# Sheet1.net
KiCad netlist of a schematic drawn in Altium Designer
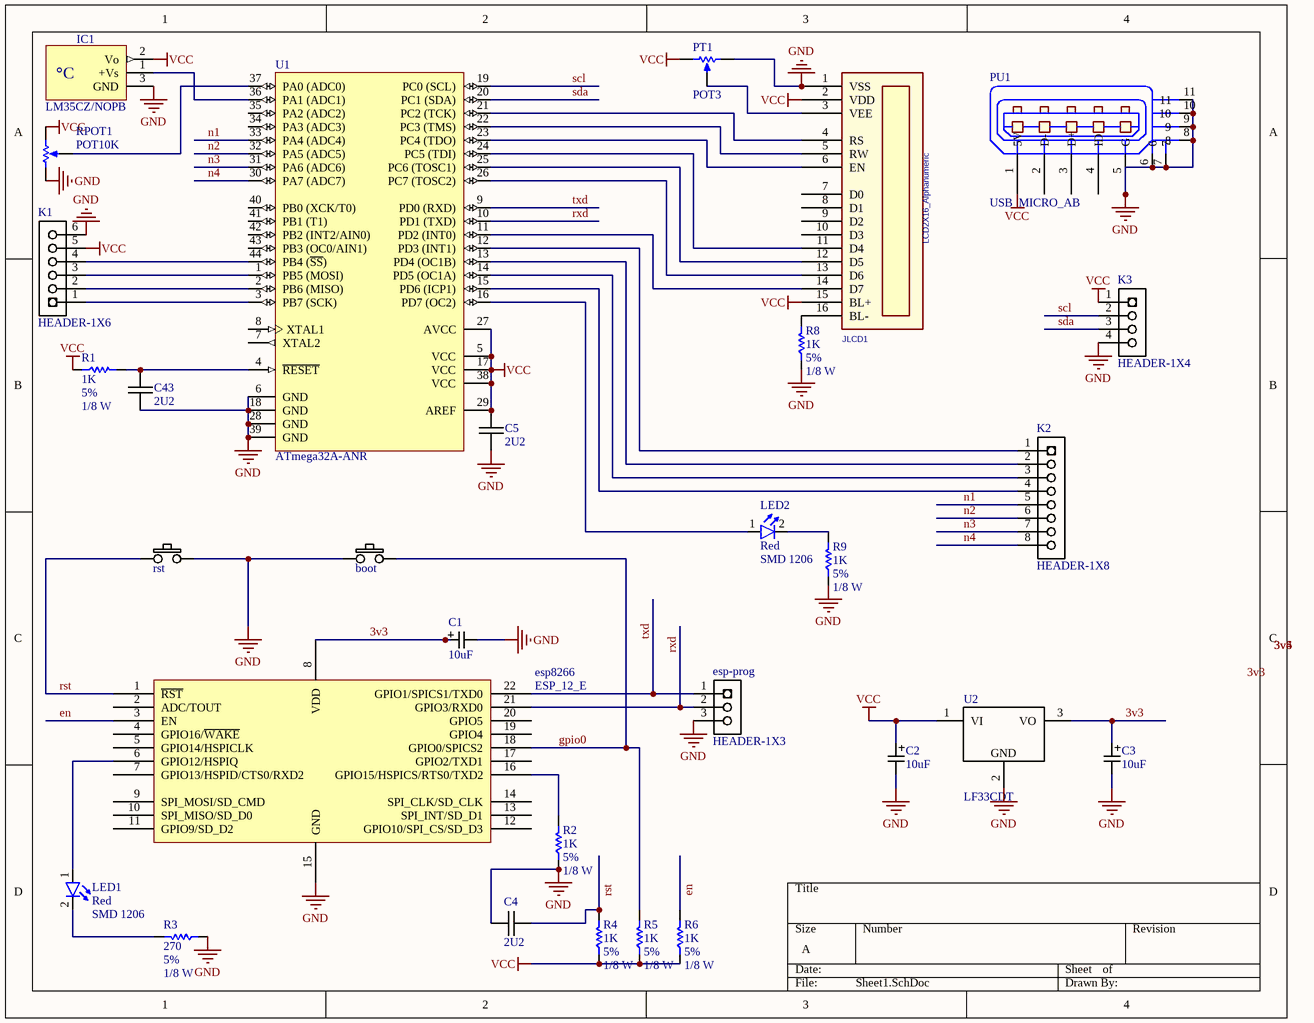
[diagram p0: Sheet1.SchDoc]

(export (version "E")
  (design (tool "Eeschema 10.0.6"))
  (components
    (comp (ref "boot")
      (value "SW-PB-BLACK-SMD")
      (footprint "SW-PB-SMD")
      (description "PUSHBUTTON SWITCH 6MM SMD")
      (libsource (lib "vh_altium_library") (part "SW-PB-BLACK-SMD"))
    )
    (comp (ref "C1")
      (value "10uF")
      (footprint "CAP-B")
      (description "tantalium capacitor")
      (fields (field (name "VOLTAGE") "16V"))
      (libsource (lib "amir_altium_lib") (part "cap"))
    )
    (comp (ref "C2")
      (value "10uF")
      (footprint "CAP-B")
      (description "tantalium capacitor")
      (fields (field (name "VOLTAGE") "16V"))
      (libsource (lib "amir_altium_lib") (part "cap"))
    )
    (comp (ref "C3")
      (value "10uF")
      (footprint "CAP-B")
      (description "tantalium capacitor")
      (fields (field (name "VOLTAGE") "16V"))
      (libsource (lib "amir_altium_lib") (part "cap"))
    )
    (comp (ref "C4")
      (value "2U2")
      (footprint "1206C-GENERIC")
      (description "CAPACITOR 0603 CERAMIC")
      (libsource (lib "vh_altium_library") (part "1206C-2U2-50V"))
    )
    (comp (ref "C5")
      (value "2U2")
      (footprint "1206C-GENERIC")
      (description "CAPACITOR 0603 CERAMIC")
      (libsource (lib "vh_altium_library") (part "1206C-2U2-50V"))
    )
    (comp (ref "C43")
      (value "2U2")
      (footprint "1206C-GENERIC")
      (description "CAPACITOR 0603 CERAMIC")
      (libsource (lib "vh_altium_library") (part "1206C-2U2-50V"))
    )
    (comp (ref "esp-prog")
      (value "HEADER-1X3")
      (footprint "HEADER-1X3")
      (libsource (lib "vh_altium_library") (part "HEADER-1X3"))
    )
    (comp (ref "esp8266")
      (value "ESP_12_E")
      (footprint "ESP_12_E")
      (description "ESP-12 Wi-Fi Module by AI-Thinker")
      (libsource (lib "Morteza lib") (part "ESP_12_E"))
    )
    (comp (ref "IC1")
      (value "LM35CZ/NOPB")
      (footprint "TO-92AA-P127")
      (description "Precision Centigrade Temperature Sensor")
      (fields (field (name "MANUFACTURER") "NATIONAL SEMICONDUCTOR") (field (name "AUTHOR") "CERN DEM JLC"))
      (libsource (lib "Sensors") (part "LM35CZ/NOPB"))
    )
    (comp (ref "JLCD1") (value "LCD2X16_Alphanumeric") (libsource (lib "ALL") (part "LCD2X16_Alphanumeric")))
    (comp (ref "K1")
      (value "HEADER-1X6")
      (footprint "HEADER-1X6")
      (libsource (lib "vh_altium_library") (part "HEADER-1X6"))
    )
    (comp (ref "K2")
      (value "HEADER-1X8")
      (footprint "HEADER-1X8")
      (libsource (lib "vh_altium_library") (part "HEADER-1X8"))
    )
    (comp (ref "K3")
      (value "HEADER-1X4")
      (footprint "HEADER-1X4")
      (libsource (lib "vh_altium_library") (part "HEADER-1X4"))
    )
    (comp (ref "LED1")
      (value "Red")
      (footprint "LED SMD 1206")
      (description "LED")
      (fields
        (field (name "COLOR") "Red")
        (field (name "SIZE") "SMD 1206")
        (field (name "DESIGNER") "Saeid Jorablo")
      )
      (libsource (lib "Electrovolt Lib") (part "LED"))
    )
    (comp (ref "LED2")
      (value "Red")
      (footprint "LED SMD 1206")
      (description "LED")
      (fields
        (field (name "COLOR") "Red")
        (field (name "SIZE") "SMD 1206")
        (field (name "DESIGNER") "Saeid Jorablo")
      )
      (libsource (lib "Electrovolt Lib") (part "LED"))
    )
    (comp (ref "PT1")
      (value "POT3")
      (footprint "POT3")
      (description "Variable Potentiometer top adjust")
      (fields (field (name "DESIGNER") "Seyed Mohsen Ghasemian"))
      (libsource (lib "usefully_Library") (part "POT3"))
    )
    (comp (ref "PU1")
      (value "USB_MICRO_AB")
      (footprint "UUSB_AB_BM_SHS")
      (libsource (lib "ALL") (part "USB_MICRO_AB"))
    )
    (comp (ref "R1")
      (value "1K")
      (footprint "RES 1206 (3216X08L)")
      (description "Resistor")
      (fields (field (name "TOLERANCE") "5%") (field (name "POWER") "1/8 W"))
      (libsource (lib "Electrovolt Lib") (part "Resistor"))
    )
    (comp (ref "R2")
      (value "1K")
      (footprint "RES 1206 (3216X08L)")
      (description "Resistor")
      (fields (field (name "TOLERANCE") "5%") (field (name "POWER") "1/8 W"))
      (libsource (lib "Electrovolt Lib") (part "Resistor"))
    )
    (comp (ref "R3")
      (value "270")
      (footprint "RES 1206 (3216X08L)")
      (description "Resistor")
      (fields (field (name "TOLERANCE") "5%") (field (name "POWER") "1/8 W"))
      (libsource (lib "Electrovolt Lib") (part "Resistor"))
    )
    (comp (ref "R4")
      (value "1K")
      (footprint "RES 1206 (3216X08L)")
      (description "Resistor")
      (fields (field (name "TOLERANCE") "5%") (field (name "POWER") "1/8 W"))
      (libsource (lib "Electrovolt Lib") (part "Resistor"))
    )
    (comp (ref "R5")
      (value "1K")
      (footprint "RES 1206 (3216X08L)")
      (description "Resistor")
      (fields (field (name "TOLERANCE") "5%") (field (name "POWER") "1/8 W"))
      (libsource (lib "Electrovolt Lib") (part "Resistor"))
    )
    (comp (ref "R6")
      (value "1K")
      (footprint "RES 1206 (3216X08L)")
      (description "Resistor")
      (fields (field (name "TOLERANCE") "5%") (field (name "POWER") "1/8 W"))
      (libsource (lib "Electrovolt Lib") (part "Resistor"))
    )
    (comp (ref "R8")
      (value "1K")
      (footprint "RES 1206 (3216X08L)")
      (description "Resistor")
      (fields (field (name "TOLERANCE") "5%") (field (name "POWER") "1/8 W"))
      (libsource (lib "Electrovolt Lib") (part "Resistor"))
    )
    (comp (ref "R9")
      (value "1K")
      (footprint "RES 1206 (3216X08L)")
      (description "Resistor")
      (fields (field (name "TOLERANCE") "5%") (field (name "POWER") "1/8 W"))
      (libsource (lib "Electrovolt Lib") (part "Resistor"))
    )
    (comp (ref "RPOT1")
      (value "POT10K")
      (footprint "VOL_R")
      (description "Potentiometer")
      (fields (field (name "PUBLISHER") "Altium Limited"))
      (libsource (lib "ALL") (part "RPot"))
    )
    (comp (ref "rst")
      (value "SW-PB-BLACK-SMD")
      (footprint "SW-PB-SMD")
      (description "PUSHBUTTON SWITCH 6MM SMD")
      (libsource (lib "vh_altium_library") (part "SW-PB-BLACK-SMD"))
    )
    (comp (ref "U1")
      (value "ATmega32A-ANR")
      (footprint "44A_N")
      (libsource (lib "Atmel Microcontroller megaAVR") (part "ATmega32A-ANR"))
    )
    (comp (ref "U2")
      (value "LF33CDT")
      (footprint "DPAK")
      (description "Low Drop Voltage Regulator 3.3V")
      (libsource (lib "vh_altium_library") (part "LF33CDT"))
    )
  )
  (nets
    (net (code "1") (name "/3v3") (class "Default")
      (node (ref "C1") (pin "1") (pintype "passive"))
      (node (ref "C3") (pin "1") (pintype "passive"))
      (node (ref "U2") (pin "3") (pinfunction "VO_3") (pintype "passive"))
      (node (ref "esp8266") (pin "8") (pinfunction "VDD_8") (pintype "passive"))
    )
    (net (code "3") (name "/en") (class "Default")
      (node (ref "R6") (pin "2") (pinfunction "2_2") (pintype "passive"))
      (node (ref "esp8266") (pin "3") (pinfunction "EN_3") (pintype "passive"))
    )
    (net (code "4") (name "/gpio0") (class "Default")
      (node (ref "R5") (pin "2") (pinfunction "2_2") (pintype "passive"))
      (node (ref "boot") (pin "2") (pintype "passive"))
      (node (ref "esp8266") (pin "18") (pinfunction "GPIO0/SPICS2_18") (pintype "passive"))
    )
    (net (code "5") (name "/n1") (class "Default")
      (node (ref "K2") (pin "5") (pintype "passive"))
      (node (ref "U1") (pin "33") (pinfunction "PA4_(ADC4)_33") (pintype "bidirectional"))
    )
    (net (code "6") (name "/n2") (class "Default")
      (node (ref "K2") (pin "6") (pintype "passive"))
      (node (ref "U1") (pin "32") (pinfunction "PA5_(ADC5)_32") (pintype "bidirectional"))
    )
    (net (code "7") (name "/n3") (class "Default")
      (node (ref "K2") (pin "7") (pintype "passive"))
      (node (ref "U1") (pin "31") (pinfunction "PA6_(ADC6)_31") (pintype "bidirectional"))
    )
    (net (code "8") (name "/n4") (class "Default")
      (node (ref "K2") (pin "8") (pintype "passive"))
      (node (ref "U1") (pin "30") (pinfunction "PA7_(ADC7)_30") (pintype "bidirectional"))
    )
    (net (code "9") (name "/rst") (class "Default")
      (node (ref "C4") (pin "1") (pintype "passive"))
      (node (ref "R4") (pin "2") (pinfunction "2_2") (pintype "passive"))
      (node (ref "esp8266") (pin "1") (pinfunction "~{RST}_1") (pintype "passive"))
      (node (ref "rst") (pin "1") (pintype "passive"))
    )
    (net (code "10") (name "/rxd") (class "Default")
      (node (ref "U1") (pin "10") (pinfunction "PD1_(TXD)_10") (pintype "bidirectional"))
      (node (ref "esp-prog") (pin "2") (pintype "passive"))
      (node (ref "esp8266") (pin "21") (pinfunction "GPIO3/RXD0_21") (pintype "passive"))
    )
    (net (code "11") (name "/scl") (class "Default")
      (node (ref "K3") (pin "2") (pintype "passive"))
      (node (ref "U1") (pin "19") (pinfunction "PC0_(SCL)_19") (pintype "bidirectional"))
    )
    (net (code "12") (name "/sda") (class "Default")
      (node (ref "K3") (pin "3") (pintype "passive"))
      (node (ref "U1") (pin "20") (pinfunction "PC1_(SDA)_20") (pintype "bidirectional"))
    )
    (net (code "13") (name "/txd") (class "Default")
      (node (ref "U1") (pin "9") (pinfunction "PD0_(RXD)_9") (pintype "bidirectional"))
      (node (ref "esp-prog") (pin "1") (pintype "passive"))
      (node (ref "esp8266") (pin "22") (pinfunction "GPIO1/SPICS1/TXD0_22") (pintype "passive"))
    )
    (net (code "14") (name "GND") (class "Default")
      (node (ref "C1") (pin "2") (pintype "passive"))
      (node (ref "C2") (pin "2") (pintype "passive"))
      (node (ref "C3") (pin "2") (pintype "passive"))
      (node (ref "C4") (pin "2") (pintype "passive"))
      (node (ref "C43") (pin "1") (pintype "passive"))
      (node (ref "C5") (pin "1") (pintype "passive"))
      (node (ref "IC1") (pin "3") (pinfunction "GND_3") (pintype "power_in"))
      (node (ref "JLCD1") (pin "1") (pinfunction "VSS_1") (pintype "passive"))
      (node (ref "K1") (pin "6") (pintype "passive"))
      (node (ref "K3") (pin "4") (pintype "passive"))
      (node (ref "PT1") (pin "2") (pinfunction "BOT_2") (pintype "passive"))
      (node (ref "PU1") (pin "10") (pinfunction "10_10") (pintype "passive"))
      (node (ref "PU1") (pin "11") (pinfunction "11_11") (pintype "passive"))
      (node (ref "PU1") (pin "5") (pinfunction "G_5") (pintype "passive"))
      (node (ref "PU1") (pin "6") (pinfunction "6_6") (pintype "passive"))
      (node (ref "PU1") (pin "7") (pinfunction "7_7") (pintype "passive"))
      (node (ref "PU1") (pin "8") (pinfunction "8_8") (pintype "passive"))
      (node (ref "PU1") (pin "9") (pinfunction "9_9") (pintype "passive"))
      (node (ref "R2") (pin "1") (pinfunction "1_1") (pintype "passive"))
      (node (ref "R3") (pin "1") (pinfunction "1_1") (pintype "passive"))
      (node (ref "R8") (pin "1") (pinfunction "1_1") (pintype "passive"))
      (node (ref "R9") (pin "1") (pinfunction "1_1") (pintype "passive"))
      (node (ref "RPOT1") (pin "1") (pinfunction "TOP_1") (pintype "passive"))
      (node (ref "U1") (pin "18") (pinfunction "GND_18") (pintype "power_in"))
      (node (ref "U1") (pin "28") (pinfunction "GND_28") (pintype "power_in"))
      (node (ref "U1") (pin "39") (pinfunction "GND_39") (pintype "power_in"))
      (node (ref "U1") (pin "6") (pinfunction "GND_6") (pintype "power_in"))
      (node (ref "U2") (pin "2") (pintype "passive"))
      (node (ref "boot") (pin "1") (pintype "passive"))
      (node (ref "esp-prog") (pin "3") (pintype "passive"))
      (node (ref "esp8266") (pin "15") (pinfunction "GND_15") (pintype "passive"))
      (node (ref "rst") (pin "2") (pintype "passive"))
    )
    (net (code "15") (name "Net-(IC1-+Vs)") (class "Default")
      (node (ref "IC1") (pin "1") (pinfunction "+Vs_1") (pintype "power_in"))
      (node (ref "U1") (pin "36") (pinfunction "PA1_(ADC1)_36") (pintype "bidirectional"))
    )
    (net (code "16") (name "Net-(JLCD1-BL-)") (class "Default")
      (node (ref "JLCD1") (pin "16") (pinfunction "BL-_16") (pintype "passive"))
      (node (ref "R8") (pin "2") (pinfunction "2_2") (pintype "passive"))
    )
    (net (code "17") (name "Net-(JLCD1-D4)") (class "Default")
      (node (ref "JLCD1") (pin "11") (pinfunction "D4_11") (pintype "passive"))
      (node (ref "U1") (pin "24") (pinfunction "PC5_(TDI)_24") (pintype "bidirectional"))
    )
    (net (code "18") (name "Net-(JLCD1-D5)") (class "Default")
      (node (ref "JLCD1") (pin "12") (pinfunction "D5_12") (pintype "passive"))
      (node (ref "U1") (pin "25") (pinfunction "PC6_(TOSC1)_25") (pintype "bidirectional"))
    )
    (net (code "19") (name "Net-(JLCD1-D6)") (class "Default")
      (node (ref "JLCD1") (pin "13") (pinfunction "D6_13") (pintype "passive"))
      (node (ref "U1") (pin "26") (pinfunction "PC7_(TOSC2)_26") (pintype "bidirectional"))
    )
    (net (code "20") (name "Net-(JLCD1-D7)") (class "Default")
      (node (ref "JLCD1") (pin "14") (pinfunction "D7_14") (pintype "passive"))
      (node (ref "U1") (pin "11") (pinfunction "PD2_(INT0)_11") (pintype "bidirectional"))
    )
    (net (code "21") (name "Net-(JLCD1-EN)") (class "Default")
      (node (ref "JLCD1") (pin "6") (pinfunction "EN_6") (pintype "passive"))
      (node (ref "U1") (pin "23") (pinfunction "PC4_(TDO)_23") (pintype "bidirectional"))
    )
    (net (code "22") (name "Net-(JLCD1-RS)") (class "Default")
      (node (ref "JLCD1") (pin "4") (pinfunction "RS_4") (pintype "passive"))
      (node (ref "U1") (pin "21") (pinfunction "PC2_(TCK)_21") (pintype "bidirectional"))
    )
    (net (code "23") (name "Net-(JLCD1-RW)") (class "Default")
      (node (ref "JLCD1") (pin "5") (pinfunction "RW_5") (pintype "passive"))
      (node (ref "U1") (pin "22") (pinfunction "PC3_(TMS)_22") (pintype "bidirectional"))
    )
    (net (code "24") (name "Net-(JLCD1-VEE)") (class "Default")
      (node (ref "JLCD1") (pin "3") (pinfunction "VEE_3") (pintype "passive"))
      (node (ref "PT1") (pin "3") (pinfunction "TAP_3") (pintype "passive"))
    )
    (net (code "25") (name "Net-(LED1-A)") (class "Default")
      (node (ref "LED1") (pin "1") (pinfunction "A_1") (pintype "passive"))
      (node (ref "esp8266") (pin "6") (pinfunction "GPIO12/HSPIQ_6") (pintype "passive"))
    )
    (net (code "26") (name "Net-(LED1-K)") (class "Default")
      (node (ref "LED1") (pin "2") (pinfunction "K_2") (pintype "passive"))
      (node (ref "R3") (pin "2") (pinfunction "2_2") (pintype "passive"))
    )
    (net (code "27") (name "Net-(LED2-A)") (class "Default")
      (node (ref "LED2") (pin "1") (pinfunction "A_1") (pintype "passive"))
      (node (ref "U1") (pin "16") (pinfunction "PD7_(OC2)_16") (pintype "bidirectional"))
    )
    (net (code "28") (name "Net-(LED2-K)") (class "Default")
      (node (ref "LED2") (pin "2") (pinfunction "K_2") (pintype "passive"))
      (node (ref "R9") (pin "2") (pinfunction "2_2") (pintype "passive"))
    )
    (net (code "29") (name "Net-(RPOT1-TAP)") (class "Default")
      (node (ref "RPOT1") (pin "2") (pinfunction "TAP_2") (pintype "passive"))
      (node (ref "U1") (pin "37") (pinfunction "PA0_(ADC0)_37") (pintype "bidirectional"))
    )
    (net (code "30") (name "Net-(U1-PB4_(~{SS}))") (class "Default")
      (node (ref "K1") (pin "4") (pintype "passive"))
      (node (ref "U1") (pin "44") (pinfunction "PB4_(~{SS})_44") (pintype "bidirectional"))
    )
    (net (code "31") (name "Net-(U1-PB5_(MOSI))") (class "Default")
      (node (ref "K1") (pin "3") (pintype "passive"))
      (node (ref "U1") (pin "1") (pinfunction "PB5_(MOSI)_1") (pintype "bidirectional"))
    )
    (net (code "32") (name "Net-(U1-PB6_(MISO))") (class "Default")
      (node (ref "K1") (pin "2") (pintype "passive"))
      (node (ref "U1") (pin "2") (pinfunction "PB6_(MISO)_2") (pintype "bidirectional"))
    )
    (net (code "33") (name "Net-(U1-PB7_(SCK))") (class "Default")
      (node (ref "K1") (pin "1") (pintype "passive"))
      (node (ref "U1") (pin "3") (pinfunction "PB7_(SCK)_3") (pintype "bidirectional"))
    )
    (net (code "34") (name "Net-(U1-PD3_(INT1))") (class "Default")
      (node (ref "K2") (pin "1") (pintype "passive"))
      (node (ref "U1") (pin "12") (pinfunction "PD3_(INT1)_12") (pintype "bidirectional"))
    )
    (net (code "35") (name "Net-(U1-PD4_(OC1B))") (class "Default")
      (node (ref "K2") (pin "2") (pintype "passive"))
      (node (ref "U1") (pin "13") (pinfunction "PD4_(OC1B)_13") (pintype "bidirectional"))
    )
    (net (code "36") (name "Net-(U1-PD5_(OC1A))") (class "Default")
      (node (ref "K2") (pin "3") (pintype "passive"))
      (node (ref "U1") (pin "14") (pinfunction "PD5_(OC1A)_14") (pintype "bidirectional"))
    )
    (net (code "37") (name "Net-(U1-PD6_(ICP1))") (class "Default")
      (node (ref "K2") (pin "4") (pintype "passive"))
      (node (ref "U1") (pin "15") (pinfunction "PD6_(ICP1)_15") (pintype "bidirectional"))
    )
    (net (code "38") (name "Net-(U1-~{RESET})") (class "Default")
      (node (ref "C43") (pin "2") (pintype "passive"))
      (node (ref "R1") (pin "2") (pinfunction "2_2") (pintype "passive"))
      (node (ref "U1") (pin "4") (pinfunction "~{RESET}_4") (pintype "input"))
    )
    (net (code "39") (name "Net-(esp8266-GPIO15{slash}HSPICS{slash}RTS0{slash}TXD2)") (class "Default")
      (node (ref "R2") (pin "2") (pinfunction "2_2") (pintype "passive"))
      (node (ref "esp8266") (pin "16") (pinfunction "GPIO15/HSPICS/RTS0/TXD2_16") (pintype "passive"))
    )
    (net (code "40") (name "VCC") (class "Default")
      (node (ref "C2") (pin "1") (pintype "passive"))
      (node (ref "C5") (pin "2") (pintype "passive"))
      (node (ref "IC1") (pin "2") (pinfunction "Vo_2") (pintype "output"))
      (node (ref "JLCD1") (pin "15") (pinfunction "BL+_15") (pintype "passive"))
      (node (ref "JLCD1") (pin "2") (pinfunction "VDD_2") (pintype "passive"))
      (node (ref "K1") (pin "5") (pintype "passive"))
      (node (ref "K3") (pin "1") (pintype "passive"))
      (node (ref "PT1") (pin "1") (pinfunction "TOP_1") (pintype "passive"))
      (node (ref "PU1") (pin "1") (pinfunction "5V_1") (pintype "passive"))
      (node (ref "R1") (pin "1") (pinfunction "1_1") (pintype "passive"))
      (node (ref "R4") (pin "1") (pinfunction "1_1") (pintype "passive"))
      (node (ref "R5") (pin "1") (pinfunction "1_1") (pintype "passive"))
      (node (ref "R6") (pin "1") (pinfunction "1_1") (pintype "passive"))
      (node (ref "RPOT1") (pin "3") (pinfunction "BOT_3") (pintype "passive"))
      (node (ref "U1") (pin "17") (pinfunction "VCC_17") (pintype "power_in"))
      (node (ref "U1") (pin "27") (pinfunction "AVCC_27") (pintype "power_in"))
      (node (ref "U1") (pin "29") (pinfunction "AREF_29") (pintype "power_in"))
      (node (ref "U1") (pin "38") (pinfunction "VCC_38") (pintype "power_in"))
      (node (ref "U1") (pin "5") (pinfunction "VCC_5") (pintype "power_in"))
      (node (ref "U2") (pin "1") (pinfunction "VI_1") (pintype "passive"))
    )
    (net (code "41") (name "unconnected-(JLCD1-D0-Pad7)") (class "Default")
      (node (ref "JLCD1") (pin "7") (pinfunction "D0_7") (pintype "passive"))
    )
    (net (code "42") (name "unconnected-(JLCD1-D1-Pad8)") (class "Default")
      (node (ref "JLCD1") (pin "8") (pinfunction "D1_8") (pintype "passive"))
    )
    (net (code "43") (name "unconnected-(JLCD1-D2-Pad9)") (class "Default")
      (node (ref "JLCD1") (pin "9") (pinfunction "D2_9") (pintype "passive"))
    )
    (net (code "44") (name "unconnected-(JLCD1-D3-Pad10)") (class "Default")
      (node (ref "JLCD1") (pin "10") (pinfunction "D3_10") (pintype "passive"))
    )
    (net (code "45") (name "unconnected-(PU1-D+-Pad3)") (class "Default")
      (node (ref "PU1") (pin "3") (pinfunction "D+_3") (pintype "passive"))
    )
    (net (code "46") (name "unconnected-(PU1-D--Pad2)") (class "Default")
      (node (ref "PU1") (pin "2") (pinfunction "D-_2") (pintype "passive"))
    )
    (net (code "47") (name "unconnected-(PU1-ID-Pad4)") (class "Default")
      (node (ref "PU1") (pin "4") (pinfunction "ID_4") (pintype "passive"))
    )
    (net (code "48") (name "unconnected-(U1-PA2_(ADC2)-Pad35)") (class "Default")
      (node (ref "U1") (pin "35") (pinfunction "PA2_(ADC2)_35") (pintype "bidirectional"))
    )
    (net (code "49") (name "unconnected-(U1-PA3_(ADC3)-Pad34)") (class "Default")
      (node (ref "U1") (pin "34") (pinfunction "PA3_(ADC3)_34") (pintype "bidirectional"))
    )
    (net (code "50") (name "unconnected-(U1-PB0_(XCK{slash}T0)-Pad40)") (class "Default")
      (node (ref "U1") (pin "40") (pinfunction "PB0_(XCK/T0)_40") (pintype "bidirectional"))
    )
    (net (code "51") (name "unconnected-(U1-PB1_(T1)-Pad41)") (class "Default")
      (node (ref "U1") (pin "41") (pinfunction "PB1_(T1)_41") (pintype "bidirectional"))
    )
    (net (code "52") (name "unconnected-(U1-PB2_(INT2{slash}AIN0)-Pad42)") (class "Default")
      (node (ref "U1") (pin "42") (pinfunction "PB2_(INT2/AIN0)_42") (pintype "bidirectional"))
    )
    (net (code "53") (name "unconnected-(U1-PB3_(OC0{slash}AIN1)-Pad43)") (class "Default")
      (node (ref "U1") (pin "43") (pinfunction "PB3_(OC0/AIN1)_43") (pintype "bidirectional"))
    )
    (net (code "54") (name "unconnected-(U1-XTAL1-Pad8)") (class "Default")
      (node (ref "U1") (pin "8") (pinfunction "XTAL1_8") (pintype "input"))
    )
    (net (code "55") (name "unconnected-(U1-XTAL2-Pad7)") (class "Default")
      (node (ref "U1") (pin "7") (pinfunction "XTAL2_7") (pintype "output"))
    )
    (net (code "56") (name "unconnected-(esp8266-ADC{slash}TOUT-Pad2)") (class "Default")
      (node (ref "esp8266") (pin "2") (pinfunction "ADC/TOUT_2") (pintype "passive"))
    )
    (net (code "57") (name "unconnected-(esp8266-GPIO2{slash}TXD1-Pad17)") (class "Default")
      (node (ref "esp8266") (pin "17") (pinfunction "GPIO2/TXD1_17") (pintype "passive"))
    )
    (net (code "58") (name "unconnected-(esp8266-GPIO4-Pad19)") (class "Default")
      (node (ref "esp8266") (pin "19") (pinfunction "GPIO4_19") (pintype "passive"))
    )
    (net (code "59") (name "unconnected-(esp8266-GPIO5-Pad20)") (class "Default")
      (node (ref "esp8266") (pin "20") (pinfunction "GPIO5_20") (pintype "passive"))
    )
    (net (code "60") (name "unconnected-(esp8266-GPIO9{slash}SD_D2-Pad11)") (class "Default")
      (node (ref "esp8266") (pin "11") (pinfunction "GPIO9/SD_D2_11") (pintype "passive"))
    )
    (net (code "61") (name "unconnected-(esp8266-GPIO10{slash}SPI_CS{slash}SD_D3-Pad12)") (class "Default")
      (node (ref "esp8266") (pin "12") (pinfunction "GPIO10/SPI_CS/SD_D3_12") (pintype "passive"))
    )
    (net (code "62") (name "unconnected-(esp8266-GPIO13{slash}HSPID{slash}CTS0{slash}RXD2-Pad7)") (class "Default")
      (node (ref "esp8266") (pin "7") (pinfunction "GPIO13/HSPID/CTS0/RXD2_7") (pintype "passive"))
    )
    (net (code "63") (name "unconnected-(esp8266-GPIO14{slash}HSPICLK-Pad5)") (class "Default")
      (node (ref "esp8266") (pin "5") (pinfunction "GPIO14/HSPICLK_5") (pintype "passive"))
    )
    (net (code "64") (name "unconnected-(esp8266-GPIO16{slash}~{WAKE}-Pad4)") (class "Default")
      (node (ref "esp8266") (pin "4") (pinfunction "GPIO16/~{WAKE}_4") (pintype "passive"))
    )
    (net (code "65") (name "unconnected-(esp8266-SPI_CLK{slash}SD_CLK-Pad14)") (class "Default")
      (node (ref "esp8266") (pin "14") (pinfunction "SPI_CLK/SD_CLK_14") (pintype "passive"))
    )
    (net (code "66") (name "unconnected-(esp8266-SPI_INT{slash}SD_D1-Pad13)") (class "Default")
      (node (ref "esp8266") (pin "13") (pinfunction "SPI_INT/SD_D1_13") (pintype "passive"))
    )
    (net (code "67") (name "unconnected-(esp8266-SPI_MISO{slash}SD_D0-Pad10)") (class "Default")
      (node (ref "esp8266") (pin "10") (pinfunction "SPI_MISO/SD_D0_10") (pintype "passive"))
    )
    (net (code "68") (name "unconnected-(esp8266-SPI_MOSI{slash}SD_CMD-Pad9)") (class "Default")
      (node (ref "esp8266") (pin "9") (pinfunction "SPI_MOSI/SD_CMD_9") (pintype "passive"))
    )
  )
)
